# vibhub_0_1.net
KiCad netlist of a schematic drawn in EAGLE
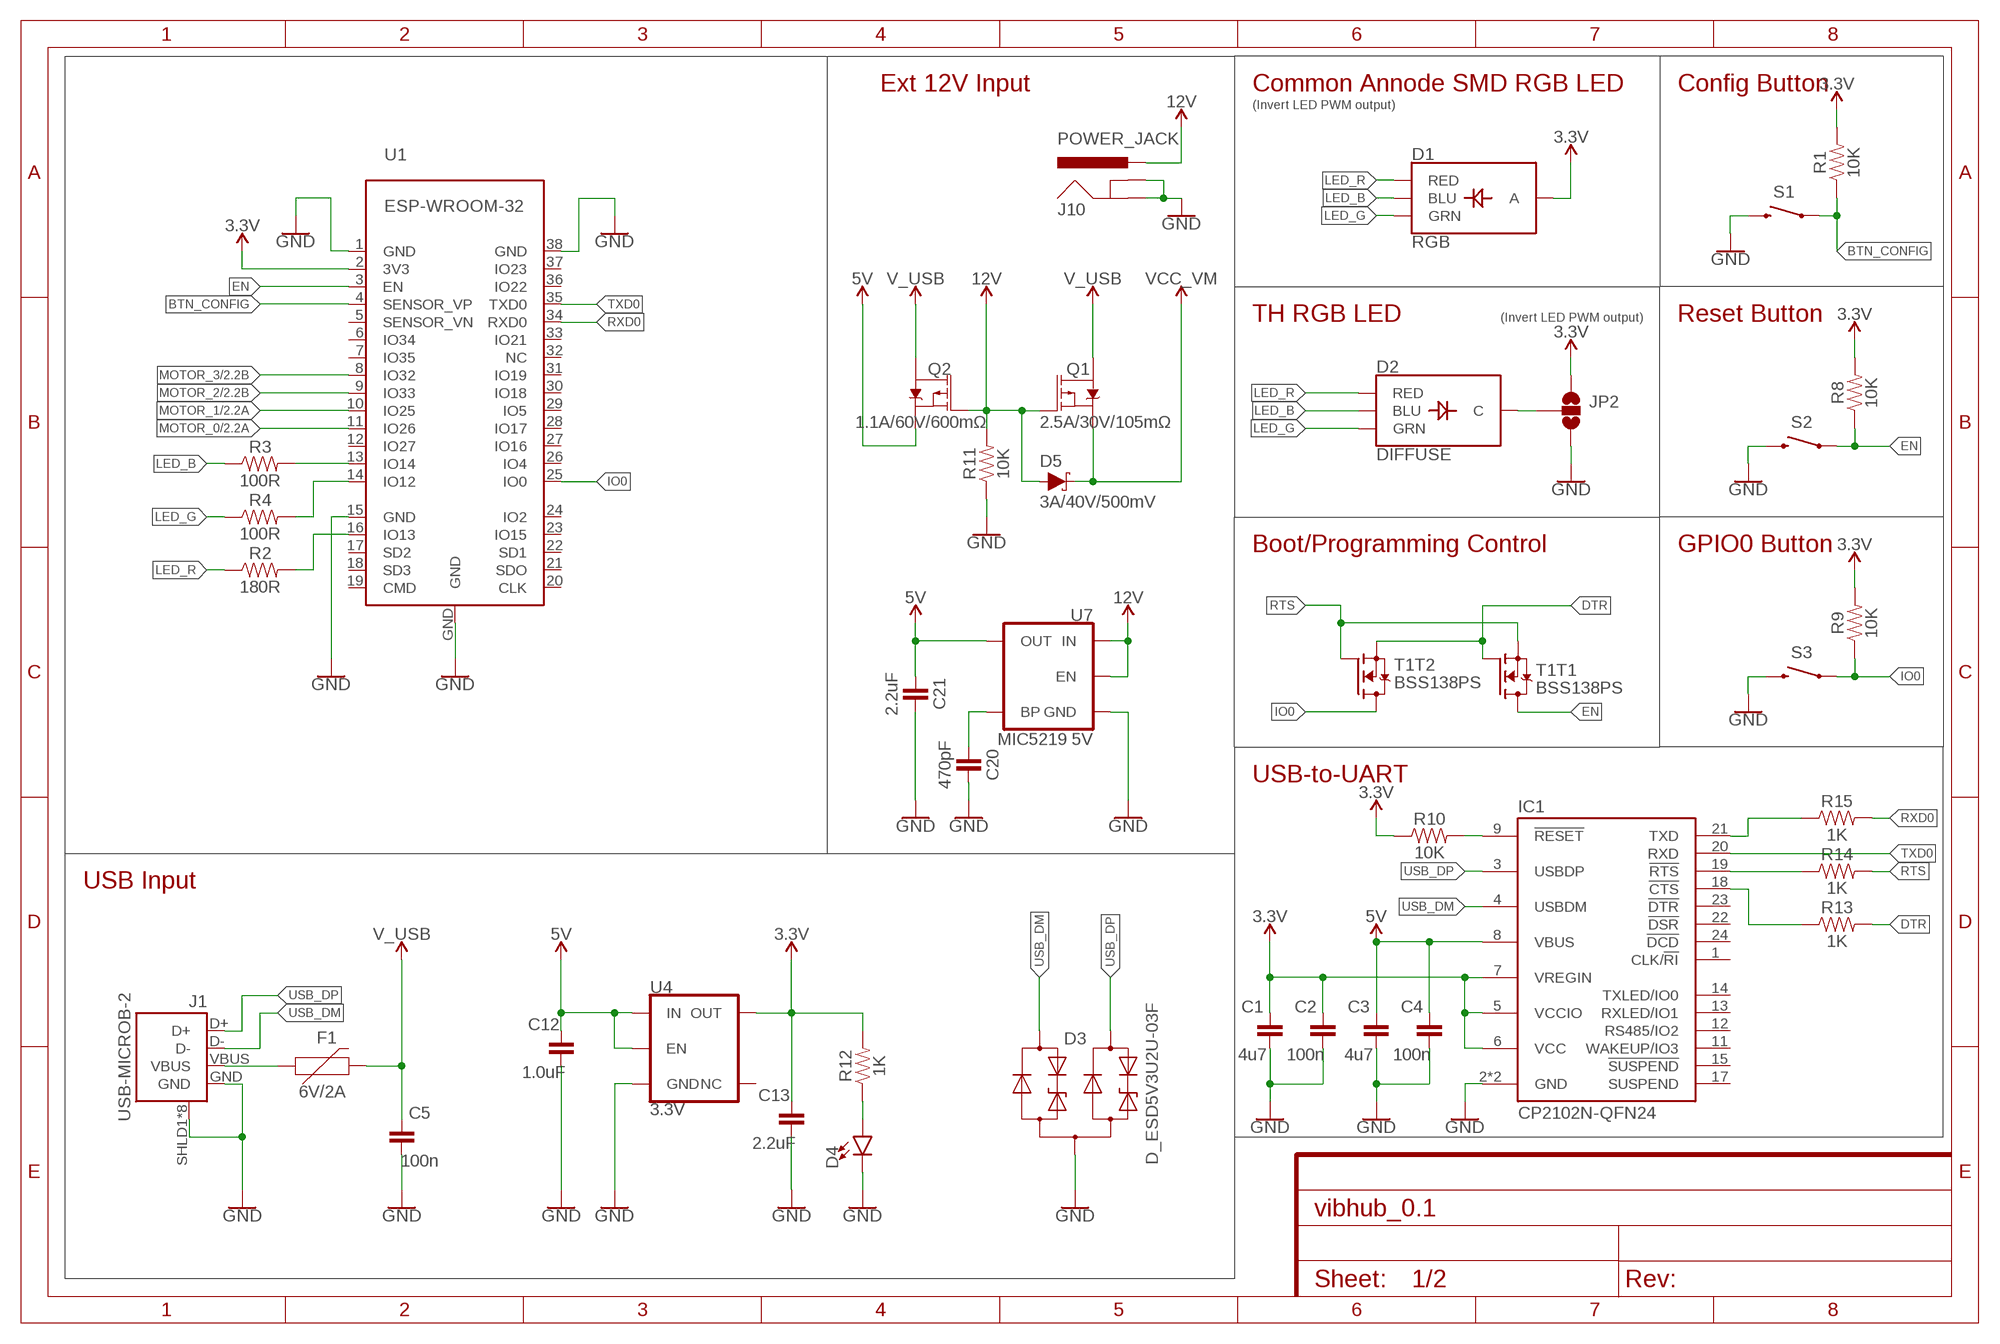
[diagram p0: schematic, sheet 1]
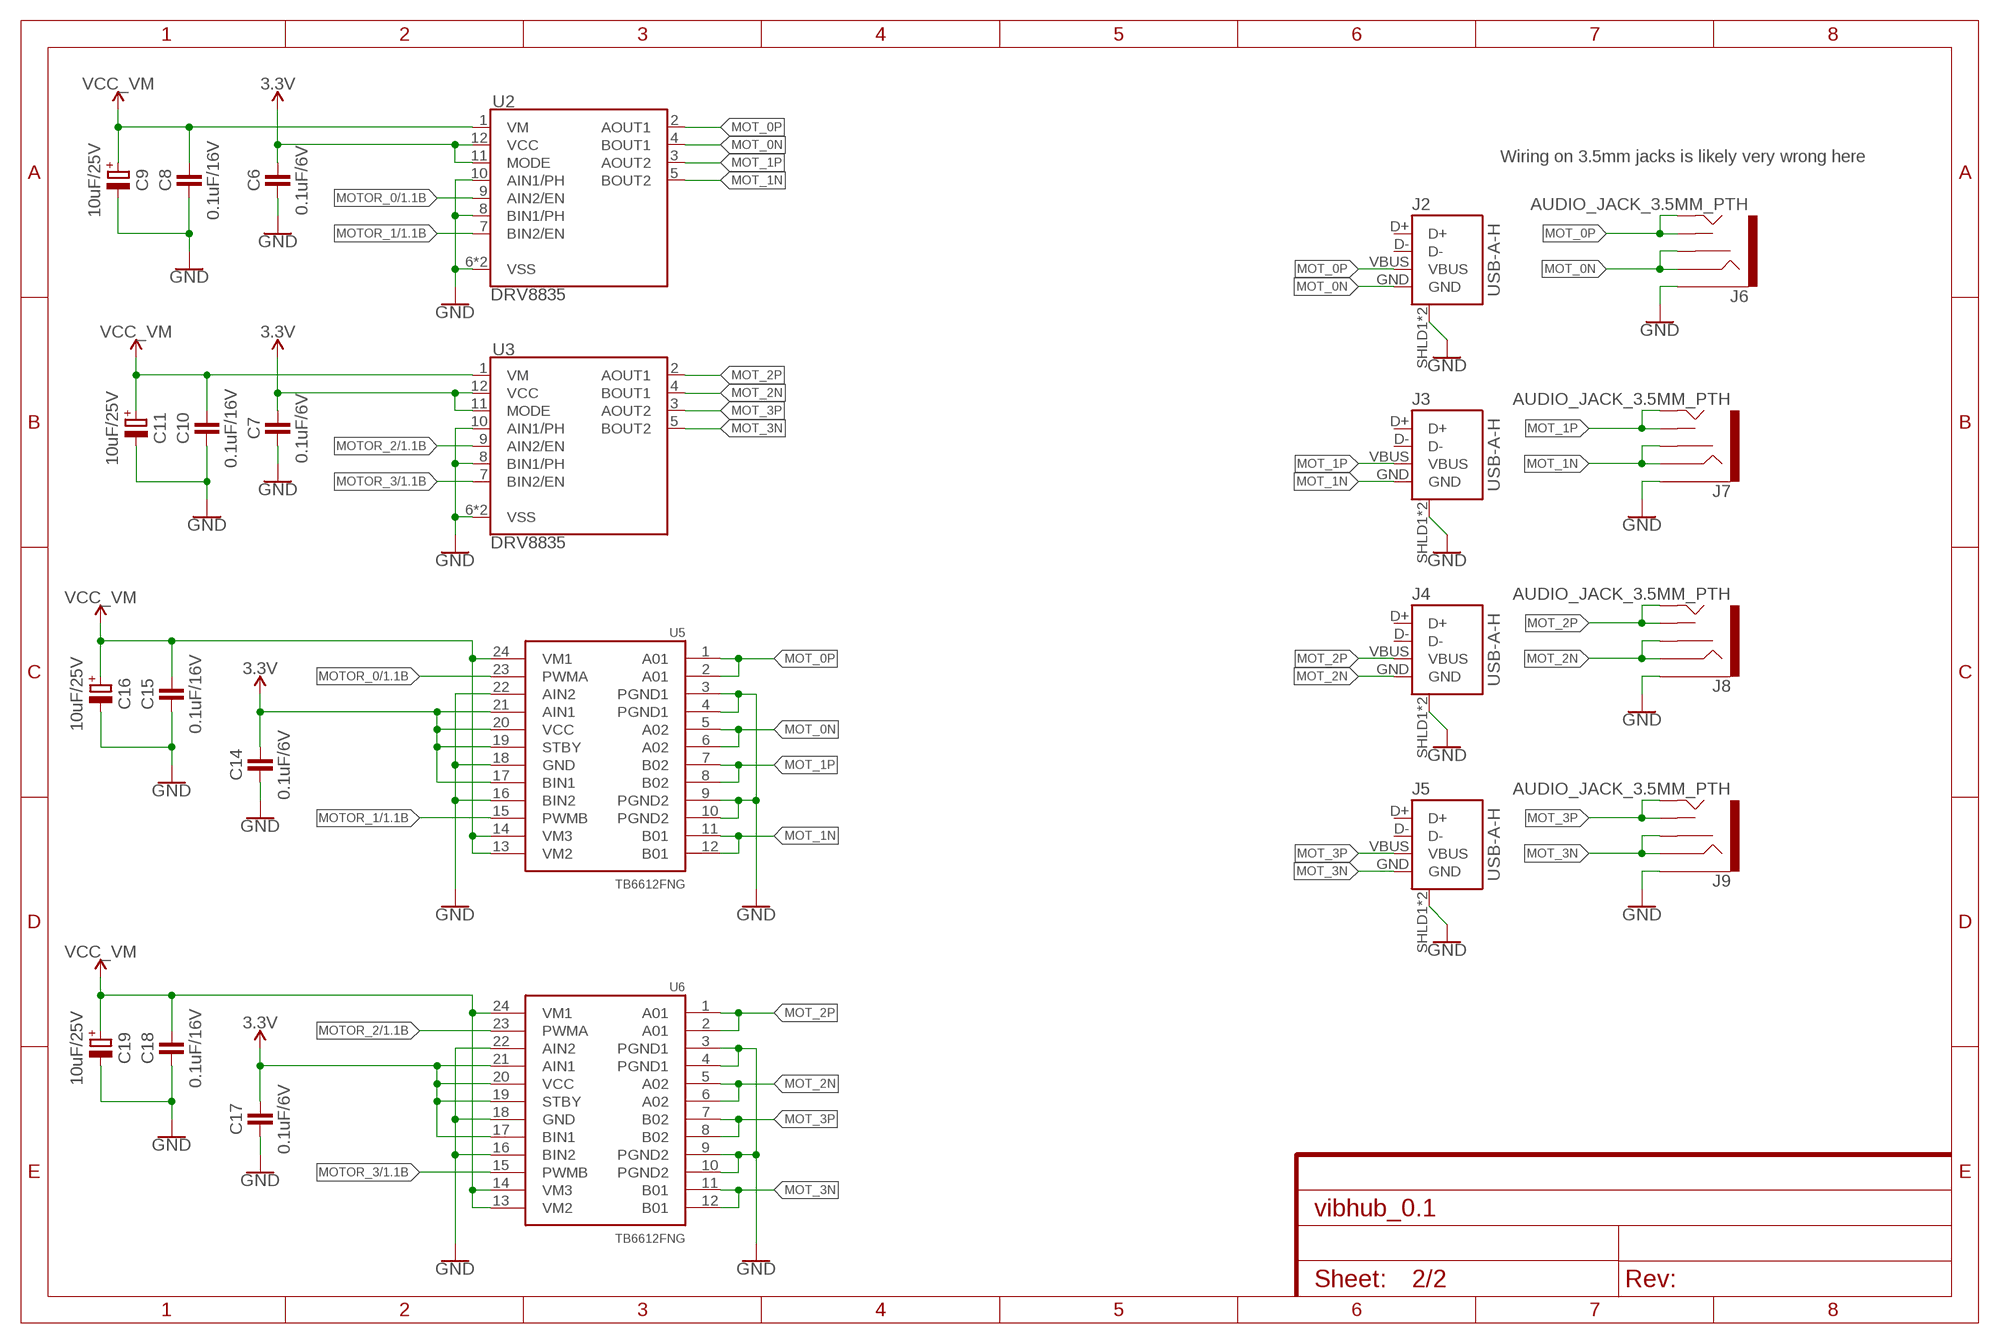
[diagram p1: schematic, sheet 2]

(export (version "E")
  (design (tool "Eeschema 10.0.6"))
  (components
    (comp (ref "C1")
      (value "4u7")
      (footprint "eagle-import:C1206")
      (libsource (lib "eagle-import") (part "CAPACITOR-1206"))
    )
    (comp (ref "C2")
      (value "100n")
      (footprint "eagle-import:C1206")
      (libsource (lib "eagle-import") (part "CAPACITOR-1206"))
    )
    (comp (ref "C3")
      (value "4u7")
      (footprint "eagle-import:C1206")
      (libsource (lib "eagle-import") (part "CAPACITOR-1206"))
    )
    (comp (ref "C4")
      (value "100n")
      (footprint "eagle-import:C1206")
      (libsource (lib "eagle-import") (part "CAPACITOR-1206"))
    )
    (comp (ref "C5")
      (value "100n")
      (footprint "eagle-import:C1206")
      (libsource (lib "eagle-import") (part "CAPACITOR-1206"))
    )
    (comp (ref "C12")
      (value "1.0uF")
      (footprint "eagle-import:C0805")
      (libsource (lib "eagle-import") (part "CAPACITOR-0805"))
    )
    (comp (ref "C13")
      (value "2.2uF")
      (footprint "eagle-import:C0805")
      (libsource (lib "eagle-import") (part "CAPACITOR-0805"))
    )
    (comp (ref "C20")
      (value "470pF")
      (footprint "eagle-import:C0805")
      (libsource (lib "eagle-import") (part "CAPACITOR-0805"))
    )
    (comp (ref "C21")
      (value "2.2uF")
      (footprint "eagle-import:C0805")
      (libsource (lib "eagle-import") (part "CAPACITOR-0805"))
    )
    (comp (ref "D1")
      (value "RGB")
      (footprint "eagle-import:P-LCC-4-3")
      (libsource (lib "eagle-import") (part "LED-RGB-CAPLCC"))
    )
    (comp (ref "D2")
      (value "DIFFUSE")
      (footprint "eagle-import:LED-RGB-THRU")
      (libsource (lib "eagle-import") (part "LED-RGB-CCDIFFUSE"))
    )
    (comp (ref "D3")
      (value "D_ESD5V3U2U-03F")
      (footprint "eagle-import:SOT723")
      (libsource (lib "eagle-import") (part "D_ESD5V3U2U-03F"))
    )
    (comp (ref "D4")
      (value "LED1206")
      (footprint "eagle-import:LED-1206")
      (libsource (lib "eagle-import") (part "LED1206"))
    )
    (comp (ref "D5")
      (value "3A/40V/500mV")
      (footprint "eagle-import:SMA-DIODE")
      (libsource (lib "eagle-import") (part "DIODE-SCHOTTKY-B340A"))
    )
    (comp (ref "F1")
      (value "6V/2A")
      (footprint "eagle-import:1206")
      (libsource (lib "eagle-import") (part "PPTC_HALF-AMP"))
    )
    (comp (ref "IC1")
      (value "CP2102N-QFN24")
      (footprint "eagle-import:QFN24-PAD")
      (libsource (lib "eagle-import") (part "CP2102N-QFN24"))
    )
    (comp (ref "J1")
      (value "USB-MICROB-2")
      (footprint "eagle-import:USB-MICROB-10118194")
      (libsource (lib "eagle-import") (part "USB-MICROB-2"))
    )
    (comp (ref "J10")
      (value "POWER_JACK")
      (footprint "eagle-import:POWER_JACK_PTH")
      (libsource (lib "eagle-import") (part "POWER_JACK"))
    )
    (comp (ref "JP2")
      (value "JUMPER-SMT_3_NO_SILK")
      (footprint "eagle-import:SMT-JUMPER_3_NO_SILK")
      (libsource (lib "eagle-import") (part "JUMPER-SMT_3_NO_SILK"))
    )
    (comp (ref "Q1")
      (value "2.5A/30V/105mΩ")
      (footprint "eagle-import:SOT23-3")
      (libsource (lib "eagle-import") (part "MOSFET_PCH-DMG2307L"))
    )
    (comp (ref "Q2")
      (value "1.1A/60V/600mΩ")
      (footprint "eagle-import:SOT23-3")
      (libsource (lib "eagle-import") (part "MOSFET_PCH-SI2309DS"))
    )
    (comp (ref "R1")
      (value "10K")
      (footprint "eagle-import:0805")
      (libsource (lib "eagle-import") (part "RESISTOR0805"))
    )
    (comp (ref "R2")
      (value "180R")
      (footprint "eagle-import:0805")
      (libsource (lib "eagle-import") (part "RESISTOR0805"))
    )
    (comp (ref "R3")
      (value "100R")
      (footprint "eagle-import:0805")
      (libsource (lib "eagle-import") (part "RESISTOR0805"))
    )
    (comp (ref "R4")
      (value "100R")
      (footprint "eagle-import:0805")
      (libsource (lib "eagle-import") (part "RESISTOR0805"))
    )
    (comp (ref "R8")
      (value "10K")
      (footprint "eagle-import:0805")
      (libsource (lib "eagle-import") (part "RESISTOR0805"))
    )
    (comp (ref "R9")
      (value "10K")
      (footprint "eagle-import:0805")
      (libsource (lib "eagle-import") (part "RESISTOR0805"))
    )
    (comp (ref "R10")
      (value "10K")
      (footprint "eagle-import:0805")
      (libsource (lib "eagle-import") (part "RESISTOR0805"))
    )
    (comp (ref "R11")
      (value "10K")
      (footprint "eagle-import:0805")
      (libsource (lib "eagle-import") (part "RESISTOR0805"))
    )
    (comp (ref "R12")
      (value "1K")
      (footprint "eagle-import:0805")
      (libsource (lib "eagle-import") (part "RESISTOR0805"))
    )
    (comp (ref "R13")
      (value "1K")
      (footprint "eagle-import:0805")
      (libsource (lib "eagle-import") (part "RESISTOR0805"))
    )
    (comp (ref "R14")
      (value "1K")
      (footprint "eagle-import:0805")
      (libsource (lib "eagle-import") (part "RESISTOR0805"))
    )
    (comp (ref "R15")
      (value "1K")
      (footprint "eagle-import:0805")
      (libsource (lib "eagle-import") (part "RESISTOR0805"))
    )
    (comp (ref "S1")
      (value "MOMENTARY-SWITCH-SPST-PTH-6.0MM")
      (footprint "eagle-import:TACTILE_SWITCH_PTH_6.0MM")
      (libsource (lib "eagle-import") (part "MOMENTARY-SWITCH-SPST-PTH-6.0MM"))
    )
    (comp (ref "S2")
      (value "MOMENTARY-SWITCH-SPST-PTH-6.0MM")
      (footprint "eagle-import:TACTILE_SWITCH_PTH_6.0MM")
      (libsource (lib "eagle-import") (part "MOMENTARY-SWITCH-SPST-PTH-6.0MM"))
    )
    (comp (ref "S3")
      (value "MOMENTARY-SWITCH-SPST-PTH-6.0MM")
      (footprint "eagle-import:TACTILE_SWITCH_PTH_6.0MM")
      (libsource (lib "eagle-import") (part "MOMENTARY-SWITCH-SPST-PTH-6.0MM"))
    )
    (comp (ref "T1")
      (value "BSS138PS")
      (footprint "eagle-import:SOT363")
      (libsource (lib "eagle-import") (part "BSS138PS"))
    )
    (comp (ref "U1")
      (value "ESP-WROOM-32")
      (footprint "eagle-import:ESP-WROOM-32")
      (libsource (lib "eagle-import") (part "ESP-WROOM-32"))
    )
    (comp (ref "U4")
      (value "3.3V")
      (footprint "eagle-import:SOT23-5")
      (libsource (lib "eagle-import") (part "V_REG_AP2112K-3.3V"))
    )
    (comp (ref "U7")
      (value "MIC5219 5V")
      (footprint "eagle-import:SOT23-5")
      (libsource (lib "eagle-import") (part "V_REG_MIC52195V"))
    )
    (comp (ref "C6")
      (value "0.1uF/6V")
      (footprint "eagle-import:C0805")
      (libsource (lib "eagle-import") (part "CAPACITOR-0805"))
    )
    (comp (ref "C7")
      (value "0.1uF/6V")
      (footprint "eagle-import:C0805")
      (libsource (lib "eagle-import") (part "CAPACITOR-0805"))
    )
    (comp (ref "C8")
      (value "0.1uF/16V")
      (footprint "eagle-import:C1206")
      (libsource (lib "eagle-import") (part "CAPACITOR-1206"))
    )
    (comp (ref "C9")
      (value "10uF/25V")
      (footprint "eagle-import:E2-4")
      (libsource (lib "eagle-import") (part "CAPACITOR_POL-E2-4"))
    )
    (comp (ref "C10")
      (value "0.1uF/16V")
      (footprint "eagle-import:C1206")
      (libsource (lib "eagle-import") (part "CAPACITOR-1206"))
    )
    (comp (ref "C11")
      (value "10uF/25V")
      (footprint "eagle-import:E2-4")
      (libsource (lib "eagle-import") (part "CAPACITOR_POL-E2-4"))
    )
    (comp (ref "C14")
      (value "0.1uF/6V")
      (footprint "eagle-import:C0805")
      (libsource (lib "eagle-import") (part "CAPACITOR-0805"))
    )
    (comp (ref "C15")
      (value "0.1uF/16V")
      (footprint "eagle-import:C1206")
      (libsource (lib "eagle-import") (part "CAPACITOR-1206"))
    )
    (comp (ref "C16")
      (value "10uF/25V")
      (footprint "eagle-import:E2-4")
      (libsource (lib "eagle-import") (part "CAPACITOR_POL-E2-4"))
    )
    (comp (ref "C17")
      (value "0.1uF/6V")
      (footprint "eagle-import:C0805")
      (libsource (lib "eagle-import") (part "CAPACITOR-0805"))
    )
    (comp (ref "C18")
      (value "0.1uF/16V")
      (footprint "eagle-import:C1206")
      (libsource (lib "eagle-import") (part "CAPACITOR-1206"))
    )
    (comp (ref "C19")
      (value "10uF/25V")
      (footprint "eagle-import:E2-4")
      (libsource (lib "eagle-import") (part "CAPACITOR_POL-E2-4"))
    )
    (comp (ref "J2")
      (value "USB-A-H")
      (footprint "eagle-import:USB-A-H")
      (libsource (lib "eagle-import") (part "USB-A-H"))
    )
    (comp (ref "J3")
      (value "USB-A-H")
      (footprint "eagle-import:USB-A-H")
      (libsource (lib "eagle-import") (part "USB-A-H"))
    )
    (comp (ref "J4")
      (value "USB-A-H")
      (footprint "eagle-import:USB-A-H")
      (libsource (lib "eagle-import") (part "USB-A-H"))
    )
    (comp (ref "J5")
      (value "USB-A-H")
      (footprint "eagle-import:USB-A-H")
      (libsource (lib "eagle-import") (part "USB-A-H"))
    )
    (comp (ref "J6")
      (value "AUDIO_JACK_3.5MM_PTH")
      (footprint "eagle-import:AUDIO-JACK")
      (libsource (lib "eagle-import") (part "AUDIO_JACK_3.5MM_PTH"))
    )
    (comp (ref "J7")
      (value "AUDIO_JACK_3.5MM_PTH")
      (footprint "eagle-import:AUDIO-JACK")
      (libsource (lib "eagle-import") (part "AUDIO_JACK_3.5MM_PTH"))
    )
    (comp (ref "J8")
      (value "AUDIO_JACK_3.5MM_PTH")
      (footprint "eagle-import:AUDIO-JACK")
      (libsource (lib "eagle-import") (part "AUDIO_JACK_3.5MM_PTH"))
    )
    (comp (ref "J9")
      (value "AUDIO_JACK_3.5MM_PTH")
      (footprint "eagle-import:AUDIO-JACK")
      (libsource (lib "eagle-import") (part "AUDIO_JACK_3.5MM_PTH"))
    )
    (comp (ref "U2")
      (value "DRV8835")
      (footprint "eagle-import:WSON-12")
      (libsource (lib "eagle-import") (part "DRV883X"))
    )
    (comp (ref "U3")
      (value "DRV8835")
      (footprint "eagle-import:WSON-12")
      (libsource (lib "eagle-import") (part "DRV883X"))
    )
    (comp (ref "U5")
      (value "TB6612FNG")
      (footprint "eagle-import:SSOP24")
      (libsource (lib "eagle-import") (part "TB6612FNG"))
    )
    (comp (ref "U6")
      (value "TB6612FNG")
      (footprint "eagle-import:SSOP24")
      (libsource (lib "eagle-import") (part "TB6612FNG"))
    )
  )
  (nets
    (net (code "1") (name "3.3V") (class "Default")
      (node (ref "C1") (pin "1") (pinfunction "1_1") (pintype "passive"))
      (node (ref "C13") (pin "1") (pinfunction "1_1") (pintype "passive"))
      (node (ref "C14") (pin "2") (pinfunction "2_2") (pintype "passive"))
      (node (ref "C17") (pin "2") (pinfunction "2_2") (pintype "passive"))
      (node (ref "C2") (pin "1") (pinfunction "1_1") (pintype "passive"))
      (node (ref "C6") (pin "2") (pinfunction "2_2") (pintype "passive"))
      (node (ref "C7") (pin "2") (pinfunction "2_2") (pintype "passive"))
      (node (ref "D1") (pin "4") (pinfunction "A_4") (pintype "bidirectional"))
      (node (ref "IC1") (pin "5") (pinfunction "VCCIO_5") (pintype "power_in"))
      (node (ref "IC1") (pin "6") (pinfunction "VCC_6") (pintype "power_in"))
      (node (ref "IC1") (pin "7") (pinfunction "VREGIN_7") (pintype "power_in"))
      (node (ref "JP2") (pin "1") (pinfunction "1_1") (pintype "passive"))
      (node (ref "R1") (pin "2") (pinfunction "2_2") (pintype "passive"))
      (node (ref "R10") (pin "1") (pinfunction "1_1") (pintype "passive"))
      (node (ref "R12") (pin "2") (pinfunction "2_2") (pintype "passive"))
      (node (ref "R8") (pin "2") (pinfunction "2_2") (pintype "passive"))
      (node (ref "R9") (pin "2") (pinfunction "2_2") (pintype "passive"))
      (node (ref "U1") (pin "2") (pinfunction "3V3_2") (pintype "bidirectional"))
      (node (ref "U2") (pin "11") (pinfunction "MODE_11") (pintype "bidirectional"))
      (node (ref "U2") (pin "12") (pinfunction "VCC_12") (pintype "bidirectional"))
      (node (ref "U3") (pin "11") (pinfunction "MODE_11") (pintype "bidirectional"))
      (node (ref "U3") (pin "12") (pinfunction "VCC_12") (pintype "bidirectional"))
      (node (ref "U4") (pin "5") (pinfunction "OUT_5") (pintype "passive"))
      (node (ref "U5") (pin "17") (pinfunction "BIN1_17") (pintype "bidirectional"))
      (node (ref "U5") (pin "19") (pinfunction "STBY_19") (pintype "bidirectional"))
      (node (ref "U5") (pin "20") (pinfunction "VCC_20") (pintype "bidirectional"))
      (node (ref "U5") (pin "21") (pinfunction "AIN1_21") (pintype "bidirectional"))
      (node (ref "U6") (pin "17") (pinfunction "BIN1_17") (pintype "bidirectional"))
      (node (ref "U6") (pin "19") (pinfunction "STBY_19") (pintype "bidirectional"))
      (node (ref "U6") (pin "20") (pinfunction "VCC_20") (pintype "bidirectional"))
      (node (ref "U6") (pin "21") (pinfunction "AIN1_21") (pintype "bidirectional"))
    )
    (net (code "2") (name "5V") (class "Default")
      (node (ref "C12") (pin "1") (pinfunction "1_1") (pintype "passive"))
      (node (ref "C21") (pin "2") (pinfunction "2_2") (pintype "passive"))
      (node (ref "C3") (pin "1") (pinfunction "1_1") (pintype "passive"))
      (node (ref "C4") (pin "1") (pinfunction "1_1") (pintype "passive"))
      (node (ref "IC1") (pin "8") (pinfunction "VBUS_8") (pintype "power_in"))
      (node (ref "Q2") (pin "2") (pinfunction "S_2") (pintype "bidirectional"))
      (node (ref "U4") (pin "1") (pinfunction "IN_1") (pintype "input"))
      (node (ref "U4") (pin "3") (pinfunction "EN_3") (pintype "input"))
      (node (ref "U7") (pin "5") (pinfunction "OUT_5") (pintype "passive"))
    )
    (net (code "3") (name "12V") (class "Default")
      (node (ref "D5") (pin "A") (pinfunction "A_A") (pintype "passive"))
      (node (ref "J10") (pin "PWR") (pinfunction "PWR_PWR") (pintype "bidirectional"))
      (node (ref "Q1") (pin "1") (pinfunction "G_1") (pintype "bidirectional"))
      (node (ref "Q2") (pin "1") (pinfunction "G_1") (pintype "bidirectional"))
      (node (ref "R11") (pin "2") (pinfunction "2_2") (pintype "passive"))
      (node (ref "U7") (pin "1") (pinfunction "IN_1") (pintype "input"))
      (node (ref "U7") (pin "3") (pinfunction "EN_3") (pintype "input"))
    )
    (net (code "4") (name "BTN_CONFIG") (class "Default")
      (node (ref "R1") (pin "1") (pinfunction "1_1") (pintype "passive"))
      (node (ref "S1") (pin "1") (pinfunction "1_1") (pintype "passive"))
      (node (ref "U1") (pin "4") (pinfunction "SENSOR_VP_4") (pintype "bidirectional"))
    )
    (net (code "5") (name "DTR") (class "Default")
      (node (ref "R13") (pin "2") (pinfunction "2_2") (pintype "passive"))
      (node (ref "T1") (pin "2") (pinfunction "G_2") (pintype "passive"))
      (node (ref "T1") (pin "4") (pinfunction "S_4") (pintype "passive"))
    )
    (net (code "6") (name "EN") (class "Default")
      (node (ref "R8") (pin "1") (pinfunction "1_1") (pintype "passive"))
      (node (ref "S2") (pin "1") (pinfunction "1_1") (pintype "passive"))
      (node (ref "T1") (pin "6") (pinfunction "D_6") (pintype "passive"))
      (node (ref "U1") (pin "3") (pinfunction "EN_3") (pintype "bidirectional"))
    )
    (net (code "7") (name "GND") (class "Default")
      (node (ref "C1") (pin "2") (pinfunction "2_2") (pintype "passive"))
      (node (ref "C10") (pin "1") (pinfunction "1_1") (pintype "passive"))
      (node (ref "C11") (pin "-") (pinfunction "-_-") (pintype "passive"))
      (node (ref "C12") (pin "2") (pinfunction "2_2") (pintype "passive"))
      (node (ref "C13") (pin "2") (pinfunction "2_2") (pintype "passive"))
      (node (ref "C14") (pin "1") (pinfunction "1_1") (pintype "passive"))
      (node (ref "C15") (pin "1") (pinfunction "1_1") (pintype "passive"))
      (node (ref "C16") (pin "-") (pinfunction "-_-") (pintype "passive"))
      (node (ref "C17") (pin "1") (pinfunction "1_1") (pintype "passive"))
      (node (ref "C18") (pin "1") (pinfunction "1_1") (pintype "passive"))
      (node (ref "C19") (pin "-") (pinfunction "-_-") (pintype "passive"))
      (node (ref "C2") (pin "2") (pinfunction "2_2") (pintype "passive"))
      (node (ref "C20") (pin "1") (pinfunction "1_1") (pintype "passive"))
      (node (ref "C21") (pin "1") (pinfunction "1_1") (pintype "passive"))
      (node (ref "C3") (pin "2") (pinfunction "2_2") (pintype "passive"))
      (node (ref "C4") (pin "2") (pinfunction "2_2") (pintype "passive"))
      (node (ref "C5") (pin "2") (pinfunction "2_2") (pintype "passive"))
      (node (ref "C6") (pin "1") (pinfunction "1_1") (pintype "passive"))
      (node (ref "C7") (pin "1") (pinfunction "1_1") (pintype "passive"))
      (node (ref "C8") (pin "1") (pinfunction "1_1") (pintype "passive"))
      (node (ref "C9") (pin "-") (pinfunction "-_-") (pintype "passive"))
      (node (ref "D3") (pin "3") (pinfunction "A_3") (pintype "passive"))
      (node (ref "D4") (pin "C") (pinfunction "C_C") (pintype "passive"))
      (node (ref "IC1") (pin "2") (pinfunction "GND_2") (pintype "power_in"))
      (node (ref "IC1") (pin "TP") (pinfunction "GND_TP") (pintype "power_in"))
      (node (ref "J1") (pin "GND") (pinfunction "GND_GND") (pintype "power_in"))
      (node (ref "J1") (pin "SHLD1") (pinfunction "SHIELD_SHLD1") (pintype "passive"))
      (node (ref "J1") (pin "SHLD2") (pinfunction "SHIELD_SHLD2") (pintype "passive"))
      (node (ref "J1") (pin "SHLD3") (pinfunction "SHIELD_SHLD3") (pintype "passive"))
      (node (ref "J1") (pin "SHLD4") (pinfunction "SHIELD_SHLD4") (pintype "passive"))
      (node (ref "J1") (pin "SHLD5") (pinfunction "SHIELD_SHLD5") (pintype "passive"))
      (node (ref "J1") (pin "SHLD6") (pinfunction "SHIELD_SHLD6") (pintype "passive"))
      (node (ref "J1") (pin "SHLD7") (pinfunction "SHIELD_SHLD7") (pintype "passive"))
      (node (ref "J1") (pin "SHLD8") (pinfunction "SHIELD_SHLD8") (pintype "passive"))
      (node (ref "J10") (pin "GND") (pinfunction "GND_GND") (pintype "bidirectional"))
      (node (ref "J10") (pin "GNDBREAK") (pinfunction "GNDBREAK_GNDBREAK") (pintype "bidirectional"))
      (node (ref "J2") (pin "SHLD1") (pinfunction "SHIELD_SHLD1") (pintype "passive"))
      (node (ref "J2") (pin "SHLD2") (pinfunction "SHIELD_SHLD2") (pintype "passive"))
      (node (ref "J3") (pin "SHLD1") (pinfunction "SHIELD_SHLD1") (pintype "passive"))
      (node (ref "J3") (pin "SHLD2") (pinfunction "SHIELD_SHLD2") (pintype "passive"))
      (node (ref "J4") (pin "SHLD1") (pinfunction "SHIELD_SHLD1") (pintype "passive"))
      (node (ref "J4") (pin "SHLD2") (pinfunction "SHIELD_SHLD2") (pintype "passive"))
      (node (ref "J5") (pin "SHLD1") (pinfunction "SHIELD_SHLD1") (pintype "passive"))
      (node (ref "J5") (pin "SHLD2") (pinfunction "SHIELD_SHLD2") (pintype "passive"))
      (node (ref "J6") (pin "SLEEVE") (pinfunction "SLEEVE_SLEEVE") (pintype "bidirectional"))
      (node (ref "J7") (pin "SLEEVE") (pinfunction "SLEEVE_SLEEVE") (pintype "bidirectional"))
      (node (ref "J8") (pin "SLEEVE") (pinfunction "SLEEVE_SLEEVE") (pintype "bidirectional"))
      (node (ref "J9") (pin "SLEEVE") (pinfunction "SLEEVE_SLEEVE") (pintype "bidirectional"))
      (node (ref "JP2") (pin "3") (pinfunction "3_3") (pintype "passive"))
      (node (ref "R11") (pin "1") (pinfunction "1_1") (pintype "passive"))
      (node (ref "S1") (pin "3") (pinfunction "2_3") (pintype "passive"))
      (node (ref "S2") (pin "3") (pinfunction "2_3") (pintype "passive"))
      (node (ref "S3") (pin "3") (pinfunction "2_3") (pintype "passive"))
      (node (ref "U1") (pin "1") (pinfunction "GND_1") (pintype "bidirectional"))
      (node (ref "U1") (pin "15") (pinfunction "GND_15") (pintype "bidirectional"))
      (node (ref "U1") (pin "38") (pinfunction "GND_38") (pintype "bidirectional"))
      (node (ref "U1") (pin "GND") (pinfunction "GND_GND") (pintype "bidirectional"))
      (node (ref "U2") (pin "10") (pinfunction "AIN1/PH_10") (pintype "bidirectional"))
      (node (ref "U2") (pin "6") (pinfunction "VSS_6") (pintype "bidirectional"))
      (node (ref "U2") (pin "8") (pinfunction "BIN1/PH_8") (pintype "bidirectional"))
      (node (ref "U2") (pin "PAD") (pinfunction "VSS_PAD") (pintype "bidirectional"))
      (node (ref "U3") (pin "10") (pinfunction "AIN1/PH_10") (pintype "bidirectional"))
      (node (ref "U3") (pin "6") (pinfunction "VSS_6") (pintype "bidirectional"))
      (node (ref "U3") (pin "8") (pinfunction "BIN1/PH_8") (pintype "bidirectional"))
      (node (ref "U3") (pin "PAD") (pinfunction "VSS_PAD") (pintype "bidirectional"))
      (node (ref "U4") (pin "2") (pinfunction "GND_2") (pintype "input"))
      (node (ref "U5") (pin "10") (pinfunction "PGND2_10") (pintype "bidirectional"))
      (node (ref "U5") (pin "16") (pinfunction "BIN2_16") (pintype "bidirectional"))
      (node (ref "U5") (pin "18") (pinfunction "GND_18") (pintype "bidirectional"))
      (node (ref "U5") (pin "22") (pinfunction "AIN2_22") (pintype "bidirectional"))
      (node (ref "U5") (pin "3") (pinfunction "PGND1_3") (pintype "bidirectional"))
      (node (ref "U5") (pin "4") (pinfunction "PGND1_4") (pintype "bidirectional"))
      (node (ref "U5") (pin "9") (pinfunction "PGND2_9") (pintype "bidirectional"))
      (node (ref "U6") (pin "10") (pinfunction "PGND2_10") (pintype "bidirectional"))
      (node (ref "U6") (pin "16") (pinfunction "BIN2_16") (pintype "bidirectional"))
      (node (ref "U6") (pin "18") (pinfunction "GND_18") (pintype "bidirectional"))
      (node (ref "U6") (pin "22") (pinfunction "AIN2_22") (pintype "bidirectional"))
      (node (ref "U6") (pin "3") (pinfunction "PGND1_3") (pintype "bidirectional"))
      (node (ref "U6") (pin "4") (pinfunction "PGND1_4") (pintype "bidirectional"))
      (node (ref "U6") (pin "9") (pinfunction "PGND2_9") (pintype "bidirectional"))
      (node (ref "U7") (pin "2") (pinfunction "GND_2") (pintype "input"))
    )
    (net (code "8") (name "IO0") (class "Default")
      (node (ref "R9") (pin "1") (pinfunction "1_1") (pintype "passive"))
      (node (ref "S3") (pin "1") (pinfunction "1_1") (pintype "passive"))
      (node (ref "T1") (pin "3") (pinfunction "D_3") (pintype "passive"))
      (node (ref "U1") (pin "25") (pinfunction "IO0_25") (pintype "bidirectional"))
    )
    (net (code "9") (name "LED_B") (class "Default")
      (node (ref "D1") (pin "3") (pinfunction "BLU_3") (pintype "bidirectional"))
      (node (ref "D2") (pin "4") (pinfunction "BLU_4") (pintype "bidirectional"))
      (node (ref "R3") (pin "1") (pinfunction "1_1") (pintype "passive"))
    )
    (net (code "10") (name "LED_G") (class "Default")
      (node (ref "D1") (pin "2") (pinfunction "GRN_2") (pintype "bidirectional"))
      (node (ref "D2") (pin "3") (pinfunction "GRN_3") (pintype "bidirectional"))
      (node (ref "R4") (pin "1") (pinfunction "1_1") (pintype "passive"))
    )
    (net (code "11") (name "LED_R") (class "Default")
      (node (ref "D1") (pin "1") (pinfunction "RED_1") (pintype "bidirectional"))
      (node (ref "D2") (pin "1") (pinfunction "RED_1") (pintype "bidirectional"))
      (node (ref "R2") (pin "1") (pinfunction "1_1") (pintype "passive"))
    )
    (net (code "12") (name "MOTOR_0") (class "Default")
      (node (ref "U1") (pin "11") (pinfunction "IO26_11") (pintype "bidirectional"))
      (node (ref "U2") (pin "9") (pinfunction "AIN2/EN_9") (pintype "bidirectional"))
      (node (ref "U5") (pin "23") (pinfunction "PWMA_23") (pintype "bidirectional"))
    )
    (net (code "13") (name "MOTOR_1") (class "Default")
      (node (ref "U1") (pin "10") (pinfunction "IO25_10") (pintype "bidirectional"))
      (node (ref "U2") (pin "7") (pinfunction "BIN2/EN_7") (pintype "bidirectional"))
      (node (ref "U5") (pin "15") (pinfunction "PWMB_15") (pintype "bidirectional"))
    )
    (net (code "14") (name "MOTOR_2") (class "Default")
      (node (ref "U1") (pin "9") (pinfunction "IO33_9") (pintype "bidirectional"))
      (node (ref "U3") (pin "9") (pinfunction "AIN2/EN_9") (pintype "bidirectional"))
      (node (ref "U6") (pin "23") (pinfunction "PWMA_23") (pintype "bidirectional"))
    )
    (net (code "15") (name "MOTOR_3") (class "Default")
      (node (ref "U1") (pin "8") (pinfunction "IO32_8") (pintype "bidirectional"))
      (node (ref "U3") (pin "7") (pinfunction "BIN2/EN_7") (pintype "bidirectional"))
      (node (ref "U6") (pin "15") (pinfunction "PWMB_15") (pintype "bidirectional"))
    )
    (net (code "16") (name "MOT_0N") (class "Default")
      (node (ref "J2") (pin "GND") (pinfunction "GND_GND") (pintype "power_in"))
      (node (ref "J6") (pin "RING") (pinfunction "RING_RING") (pintype "bidirectional"))
      (node (ref "J6") (pin "RSH") (pinfunction "RSH_RSH") (pintype "bidirectional"))
      (node (ref "U2") (pin "4") (pinfunction "BOUT1_4") (pintype "bidirectional"))
      (node (ref "U5") (pin "5") (pinfunction "A02_5") (pintype "bidirectional"))
      (node (ref "U5") (pin "6") (pinfunction "A02_6") (pintype "bidirectional"))
    )
    (net (code "17") (name "MOT_0P") (class "Default")
      (node (ref "J2") (pin "VBUS") (pinfunction "VBUS_VBUS") (pintype "power_in"))
      (node (ref "J6") (pin "TIP") (pinfunction "TIP_TIP") (pintype "bidirectional"))
      (node (ref "J6") (pin "TSH") (pinfunction "TSH_TSH") (pintype "bidirectional"))
      (node (ref "U2") (pin "2") (pinfunction "AOUT1_2") (pintype "bidirectional"))
      (node (ref "U5") (pin "1") (pinfunction "A01_1") (pintype "bidirectional"))
      (node (ref "U5") (pin "2") (pinfunction "A01_2") (pintype "bidirectional"))
    )
    (net (code "18") (name "MOT_1N") (class "Default")
      (node (ref "J3") (pin "GND") (pinfunction "GND_GND") (pintype "power_in"))
      (node (ref "J7") (pin "RING") (pinfunction "RING_RING") (pintype "bidirectional"))
      (node (ref "J7") (pin "RSH") (pinfunction "RSH_RSH") (pintype "bidirectional"))
      (node (ref "U2") (pin "5") (pinfunction "BOUT2_5") (pintype "bidirectional"))
      (node (ref "U5") (pin "11") (pinfunction "B01_11") (pintype "bidirectional"))
      (node (ref "U5") (pin "12") (pinfunction "B01_12") (pintype "bidirectional"))
    )
    (net (code "19") (name "MOT_1P") (class "Default")
      (node (ref "J3") (pin "VBUS") (pinfunction "VBUS_VBUS") (pintype "power_in"))
      (node (ref "J7") (pin "TIP") (pinfunction "TIP_TIP") (pintype "bidirectional"))
      (node (ref "J7") (pin "TSH") (pinfunction "TSH_TSH") (pintype "bidirectional"))
      (node (ref "U2") (pin "3") (pinfunction "AOUT2_3") (pintype "bidirectional"))
      (node (ref "U5") (pin "7") (pinfunction "B02_7") (pintype "bidirectional"))
      (node (ref "U5") (pin "8") (pinfunction "B02_8") (pintype "bidirectional"))
    )
    (net (code "20") (name "MOT_2N") (class "Default")
      (node (ref "J4") (pin "GND") (pinfunction "GND_GND") (pintype "power_in"))
      (node (ref "J8") (pin "RING") (pinfunction "RING_RING") (pintype "bidirectional"))
      (node (ref "J8") (pin "RSH") (pinfunction "RSH_RSH") (pintype "bidirectional"))
      (node (ref "U3") (pin "4") (pinfunction "BOUT1_4") (pintype "bidirectional"))
      (node (ref "U6") (pin "5") (pinfunction "A02_5") (pintype "bidirectional"))
      (node (ref "U6") (pin "6") (pinfunction "A02_6") (pintype "bidirectional"))
    )
    (net (code "21") (name "MOT_2P") (class "Default")
      (node (ref "J4") (pin "VBUS") (pinfunction "VBUS_VBUS") (pintype "power_in"))
      (node (ref "J8") (pin "TIP") (pinfunction "TIP_TIP") (pintype "bidirectional"))
      (node (ref "J8") (pin "TSH") (pinfunction "TSH_TSH") (pintype "bidirectional"))
      (node (ref "U3") (pin "2") (pinfunction "AOUT1_2") (pintype "bidirectional"))
      (node (ref "U6") (pin "1") (pinfunction "A01_1") (pintype "bidirectional"))
      (node (ref "U6") (pin "2") (pinfunction "A01_2") (pintype "bidirectional"))
    )
    (net (code "22") (name "MOT_3N") (class "Default")
      (node (ref "J5") (pin "GND") (pinfunction "GND_GND") (pintype "power_in"))
      (node (ref "J9") (pin "RING") (pinfunction "RING_RING") (pintype "bidirectional"))
      (node (ref "J9") (pin "RSH") (pinfunction "RSH_RSH") (pintype "bidirectional"))
      (node (ref "U3") (pin "5") (pinfunction "BOUT2_5") (pintype "bidirectional"))
      (node (ref "U6") (pin "11") (pinfunction "B01_11") (pintype "bidirectional"))
      (node (ref "U6") (pin "12") (pinfunction "B01_12") (pintype "bidirectional"))
    )
    (net (code "23") (name "MOT_3P") (class "Default")
      (node (ref "J5") (pin "VBUS") (pinfunction "VBUS_VBUS") (pintype "power_in"))
      (node (ref "J9") (pin "TIP") (pinfunction "TIP_TIP") (pintype "bidirectional"))
      (node (ref "J9") (pin "TSH") (pinfunction "TSH_TSH") (pintype "bidirectional"))
      (node (ref "U3") (pin "3") (pinfunction "AOUT2_3") (pintype "bidirectional"))
      (node (ref "U6") (pin "7") (pinfunction "B02_7") (pintype "bidirectional"))
      (node (ref "U6") (pin "8") (pinfunction "B02_8") (pintype "bidirectional"))
    )
    (net (code "24") (name "Net-(D2-C)") (class "Default")
      (node (ref "D2") (pin "2") (pinfunction "C_2") (pintype "bidirectional"))
      (node (ref "JP2") (pin "2") (pinfunction "2_2") (pintype "passive"))
    )
    (net (code "25") (name "Net-(D4-PadA)") (class "Default")
      (node (ref "D4") (pin "A") (pinfunction "A_A") (pintype "passive"))
      (node (ref "R12") (pin "1") (pinfunction "1_1") (pintype "passive"))
    )
    (net (code "26") (name "Net-(F1-Pad1)") (class "Default")
      (node (ref "F1") (pin "1") (pinfunction "1_1") (pintype "bidirectional"))
      (node (ref "J1") (pin "VBUS") (pinfunction "VBUS_VBUS") (pintype "power_in"))
    )
    (net (code "27") (name "Net-(IC1-TXD)") (class "Default")
      (node (ref "IC1") (pin "21") (pinfunction "TXD_21") (pintype "bidirectional"))
      (node (ref "R15") (pin "1") (pinfunction "1_1") (pintype "passive"))
    )
    (net (code "28") (name "Net-(IC1-~{CTS})") (class "Default")
      (node (ref "IC1") (pin "18") (pinfunction "~{CTS}_18") (pintype "bidirectional"))
      (node (ref "R13") (pin "1") (pinfunction "1_1") (pintype "passive"))
    )
    (net (code "29") (name "Net-(IC1-~{RESET})") (class "Default")
      (node (ref "IC1") (pin "9") (pinfunction "~{RESET}_9") (pintype "bidirectional"))
      (node (ref "R10") (pin "2") (pinfunction "2_2") (pintype "passive"))
    )
    (net (code "30") (name "Net-(IC1-~{RTS})") (class "Default")
      (node (ref "IC1") (pin "19") (pinfunction "~{RTS}_19") (pintype "bidirectional"))
      (node (ref "R14") (pin "1") (pinfunction "1_1") (pintype "passive"))
    )
    (net (code "31") (name "Net-(U1-IO12)") (class "Default")
      (node (ref "R4") (pin "2") (pinfunction "2_2") (pintype "passive"))
      (node (ref "U1") (pin "14") (pinfunction "IO12_14") (pintype "bidirectional"))
    )
    (net (code "32") (name "Net-(U1-IO13)") (class "Default")
      (node (ref "R2") (pin "2") (pinfunction "2_2") (pintype "passive"))
      (node (ref "U1") (pin "16") (pinfunction "IO13_16") (pintype "bidirectional"))
    )
    (net (code "33") (name "Net-(U1-IO14)") (class "Default")
      (node (ref "R3") (pin "2") (pinfunction "2_2") (pintype "passive"))
      (node (ref "U1") (pin "13") (pinfunction "IO14_13") (pintype "bidirectional"))
    )
    (net (code "34") (name "Net-(U7-BP)") (class "Default")
      (node (ref "C20") (pin "2") (pinfunction "2_2") (pintype "passive"))
      (node (ref "U7") (pin "4") (pinfunction "BP_4") (pintype "input"))
    )
    (net (code "35") (name "RTS") (class "Default")
      (node (ref "R14") (pin "2") (pinfunction "2_2") (pintype "passive"))
      (node (ref "T1") (pin "1") (pinfunction "S_1") (pintype "passive"))
      (node (ref "T1") (pin "5") (pinfunction "G_5") (pintype "passive"))
    )
    (net (code "36") (name "RXD0") (class "Default")
      (node (ref "R15") (pin "2") (pinfunction "2_2") (pintype "passive"))
      (node (ref "U1") (pin "34") (pinfunction "RXD0_34") (pintype "bidirectional"))
    )
    (net (code "37") (name "TXD0") (class "Default")
      (node (ref "IC1") (pin "20") (pinfunction "RXD_20") (pintype "bidirectional"))
      (node (ref "U1") (pin "35") (pinfunction "TXD0_35") (pintype "bidirectional"))
    )
    (net (code "38") (name "USB_DM") (class "Default")
      (node (ref "D3") (pin "1") (pinfunction "C1_1") (pintype "passive"))
      (node (ref "IC1") (pin "4") (pinfunction "USBDM_4") (pintype "bidirectional"))
      (node (ref "J1") (pin "D-") (pinfunction "D-_D-") (pintype "bidirectional"))
    )
    (net (code "39") (name "USB_DP") (class "Default")
      (node (ref "D3") (pin "2") (pinfunction "C2_2") (pintype "passive"))
      (node (ref "IC1") (pin "3") (pinfunction "USBDP_3") (pintype "bidirectional"))
      (node (ref "J1") (pin "D+") (pinfunction "D+_D+") (pintype "bidirectional"))
    )
    (net (code "40") (name "VCC_1") (class "Default")
      (node (ref "C10") (pin "2") (pinfunction "2_2") (pintype "passive"))
      (node (ref "C11") (pin "+") (pinfunction "+_+") (pintype "passive"))
      (node (ref "C15") (pin "2") (pinfunction "2_2") (pintype "passive"))
      (node (ref "C16") (pin "+") (pinfunction "+_+") (pintype "passive"))
      (node (ref "C18") (pin "2") (pinfunction "2_2") (pintype "passive"))
      (node (ref "C19") (pin "+") (pinfunction "+_+") (pintype "passive"))
      (node (ref "C8") (pin "2") (pinfunction "2_2") (pintype "passive"))
      (node (ref "C9") (pin "+") (pinfunction "+_+") (pintype "passive"))
      (node (ref "D5") (pin "C") (pinfunction "C_C") (pintype "passive"))
      (node (ref "Q1") (pin "2") (pinfunction "S_2") (pintype "bidirectional"))
      (node (ref "U2") (pin "1") (pinfunction "VM_1") (pintype "bidirectional"))
      (node (ref "U3") (pin "1") (pinfunction "VM_1") (pintype "bidirectional"))
      (node (ref "U5") (pin "13") (pinfunction "VM2_13") (pintype "bidirectional"))
      (node (ref "U5") (pin "14") (pinfunction "VM3_14") (pintype "bidirectional"))
      (node (ref "U5") (pin "24") (pinfunction "VM1_24") (pintype "bidirectional"))
      (node (ref "U6") (pin "13") (pinfunction "VM2_13") (pintype "bidirectional"))
      (node (ref "U6") (pin "14") (pinfunction "VM3_14") (pintype "bidirectional"))
      (node (ref "U6") (pin "24") (pinfunction "VM1_24") (pintype "bidirectional"))
    )
    (net (code "41") (name "V_USB") (class "Default")
      (node (ref "C5") (pin "1") (pinfunction "1_1") (pintype "passive"))
      (node (ref "F1") (pin "2") (pinfunction "2_2") (pintype "bidirectional"))
      (node (ref "Q1") (pin "3") (pinfunction "D_3") (pintype "bidirectional"))
      (node (ref "Q2") (pin "3") (pinfunction "D_3") (pintype "bidirectional"))
    )
    (net (code "42") (name "unconnected-(IC1-CLK{slash}~{RI}-Pad1)") (class "Default")
      (node (ref "IC1") (pin "1") (pinfunction "CLK/~{RI}_1") (pintype "bidirectional"))
    )
    (net (code "43") (name "unconnected-(IC1-RS485{slash}IO2-Pad12)") (class "Default")
      (node (ref "IC1") (pin "12") (pinfunction "RS485/IO2_12") (pintype "bidirectional"))
    )
    (net (code "44") (name "unconnected-(IC1-RXLED{slash}IO1-Pad13)") (class "Default")
      (node (ref "IC1") (pin "13") (pinfunction "RXLED/IO1_13") (pintype "bidirectional"))
    )
    (net (code "45") (name "unconnected-(IC1-SUSPEND-Pad17)") (class "Default")
      (node (ref "IC1") (pin "17") (pinfunction "SUSPEND_17") (pintype "bidirectional"))
    )
    (net (code "46") (name "unconnected-(IC1-TXLED{slash}IO0-Pad14)") (class "Default")
      (node (ref "IC1") (pin "14") (pinfunction "TXLED/IO0_14") (pintype "bidirectional"))
    )
    (net (code "47") (name "unconnected-(IC1-WAKEUP{slash}IO3-Pad11)") (class "Default")
      (node (ref "IC1") (pin "11") (pinfunction "WAKEUP/IO3_11") (pintype "bidirectional"))
    )
    (net (code "48") (name "unconnected-(IC1-~{DCD}-Pad24)") (class "Default")
      (node (ref "IC1") (pin "24") (pinfunction "~{DCD}_24") (pintype "bidirectional"))
    )
    (net (code "49") (name "unconnected-(IC1-~{DSR}-Pad22)") (class "Default")
      (node (ref "IC1") (pin "22") (pinfunction "~{DSR}_22") (pintype "bidirectional"))
    )
    (net (code "50") (name "unconnected-(IC1-~{DTR}-Pad23)") (class "Default")
      (node (ref "IC1") (pin "23") (pinfunction "~{DTR}_23") (pintype "bidirectional"))
    )
    (net (code "51") (name "unconnected-(IC1-~{SUSPEND}-Pad15)") (class "Default")
      (node (ref "IC1") (pin "15") (pinfunction "~{SUSPEND}_15") (pintype "bidirectional"))
    )
    (net (code "52") (name "unconnected-(J2-PadD+)") (class "Default")
      (node (ref "J2") (pin "D+") (pinfunction "D+_D+") (pintype "bidirectional"))
    )
    (net (code "53") (name "unconnected-(J2-PadD-)") (class "Default")
      (node (ref "J2") (pin "D-") (pinfunction "D-_D-") (pintype "bidirectional"))
    )
    (net (code "54") (name "unconnected-(J3-PadD+)") (class "Default")
      (node (ref "J3") (pin "D+") (pinfunction "D+_D+") (pintype "bidirectional"))
    )
    (net (code "55") (name "unconnected-(J3-PadD-)") (class "Default")
      (node (ref "J3") (pin "D-") (pinfunction "D-_D-") (pintype "bidirectional"))
    )
    (net (code "56") (name "unconnected-(J4-PadD+)") (class "Default")
      (node (ref "J4") (pin "D+") (pinfunction "D+_D+") (pintype "bidirectional"))
    )
    (net (code "57") (name "unconnected-(J4-PadD-)") (class "Default")
      (node (ref "J4") (pin "D-") (pinfunction "D-_D-") (pintype "bidirectional"))
    )
    (net (code "58") (name "unconnected-(J5-PadD+)") (class "Default")
      (node (ref "J5") (pin "D+") (pinfunction "D+_D+") (pintype "bidirectional"))
    )
    (net (code "59") (name "unconnected-(J5-PadD-)") (class "Default")
      (node (ref "J5") (pin "D-") (pinfunction "D-_D-") (pintype "bidirectional"))
    )
    (net (code "60") (name "unconnected-(U1-CLK-Pad20)") (class "Default")
      (node (ref "U1") (pin "20") (pinfunction "CLK_20") (pintype "bidirectional"))
    )
    (net (code "61") (name "unconnected-(U1-CMD-Pad19)") (class "Default")
      (node (ref "U1") (pin "19") (pinfunction "CMD_19") (pintype "bidirectional"))
    )
    (net (code "62") (name "unconnected-(U1-IO2-Pad24)") (class "Default")
      (node (ref "U1") (pin "24") (pinfunction "IO2_24") (pintype "bidirectional"))
    )
    (net (code "63") (name "unconnected-(U1-IO4-Pad26)") (class "Default")
      (node (ref "U1") (pin "26") (pinfunction "IO4_26") (pintype "bidirectional"))
    )
    (net (code "64") (name "unconnected-(U1-IO5-Pad29)") (class "Default")
      (node (ref "U1") (pin "29") (pinfunction "IO5_29") (pintype "bidirectional"))
    )
    (net (code "65") (name "unconnected-(U1-IO15-Pad23)") (class "Default")
      (node (ref "U1") (pin "23") (pinfunction "IO15_23") (pintype "bidirectional"))
    )
    (net (code "66") (name "unconnected-(U1-IO16-Pad27)") (class "Default")
      (node (ref "U1") (pin "27") (pinfunction "IO16_27") (pintype "bidirectional"))
    )
    (net (code "67") (name "unconnected-(U1-IO17-Pad28)") (class "Default")
      (node (ref "U1") (pin "28") (pinfunction "IO17_28") (pintype "bidirectional"))
    )
    (net (code "68") (name "unconnected-(U1-IO18-Pad30)") (class "Default")
      (node (ref "U1") (pin "30") (pinfunction "IO18_30") (pintype "bidirectional"))
    )
    (net (code "69") (name "unconnected-(U1-IO19-Pad31)") (class "Default")
      (node (ref "U1") (pin "31") (pinfunction "IO19_31") (pintype "bidirectional"))
    )
    (net (code "70") (name "unconnected-(U1-IO21-Pad33)") (class "Default")
      (node (ref "U1") (pin "33") (pinfunction "IO21_33") (pintype "bidirectional"))
    )
    (net (code "71") (name "unconnected-(U1-IO22-Pad36)") (class "Default")
      (node (ref "U1") (pin "36") (pinfunction "IO22_36") (pintype "bidirectional"))
    )
    (net (code "72") (name "unconnected-(U1-IO23-Pad37)") (class "Default")
      (node (ref "U1") (pin "37") (pinfunction "IO23_37") (pintype "bidirectional"))
    )
    (net (code "73") (name "unconnected-(U1-IO27-Pad12)") (class "Default")
      (node (ref "U1") (pin "12") (pinfunction "IO27_12") (pintype "bidirectional"))
    )
    (net (code "74") (name "unconnected-(U1-IO34-Pad6)") (class "Default")
      (node (ref "U1") (pin "6") (pinfunction "IO34_6") (pintype "bidirectional"))
    )
    (net (code "75") (name "unconnected-(U1-IO35-Pad7)") (class "Default")
      (node (ref "U1") (pin "7") (pinfunction "IO35_7") (pintype "bidirectional"))
    )
    (net (code "76") (name "unconnected-(U1-NC-Pad32)") (class "Default")
      (node (ref "U1") (pin "32") (pinfunction "NC_32") (pintype "bidirectional"))
    )
    (net (code "77") (name "unconnected-(U1-SD1-Pad22)") (class "Default")
      (node (ref "U1") (pin "22") (pinfunction "SD1_22") (pintype "bidirectional"))
    )
    (net (code "78") (name "unconnected-(U1-SD2-Pad17)") (class "Default")
      (node (ref "U1") (pin "17") (pinfunction "SD2_17") (pintype "bidirectional"))
    )
    (net (code "79") (name "unconnected-(U1-SD3-Pad18)") (class "Default")
      (node (ref "U1") (pin "18") (pinfunction "SD3_18") (pintype "bidirectional"))
    )
    (net (code "80") (name "unconnected-(U1-SDO-Pad21)") (class "Default")
      (node (ref "U1") (pin "21") (pinfunction "SDO_21") (pintype "bidirectional"))
    )
    (net (code "81") (name "unconnected-(U1-SENSOR_VN-Pad5)") (class "Default")
      (node (ref "U1") (pin "5") (pinfunction "SENSOR_VN_5") (pintype "bidirectional"))
    )
    (net (code "82") (name "unconnected-(U4-NC-Pad4)") (class "Default")
      (node (ref "U4") (pin "4") (pinfunction "NC_4") (pintype "no_connect"))
    )
  )
)
